# driverboard-v3.net
KiCad netlist of a schematic drawn in EAGLE
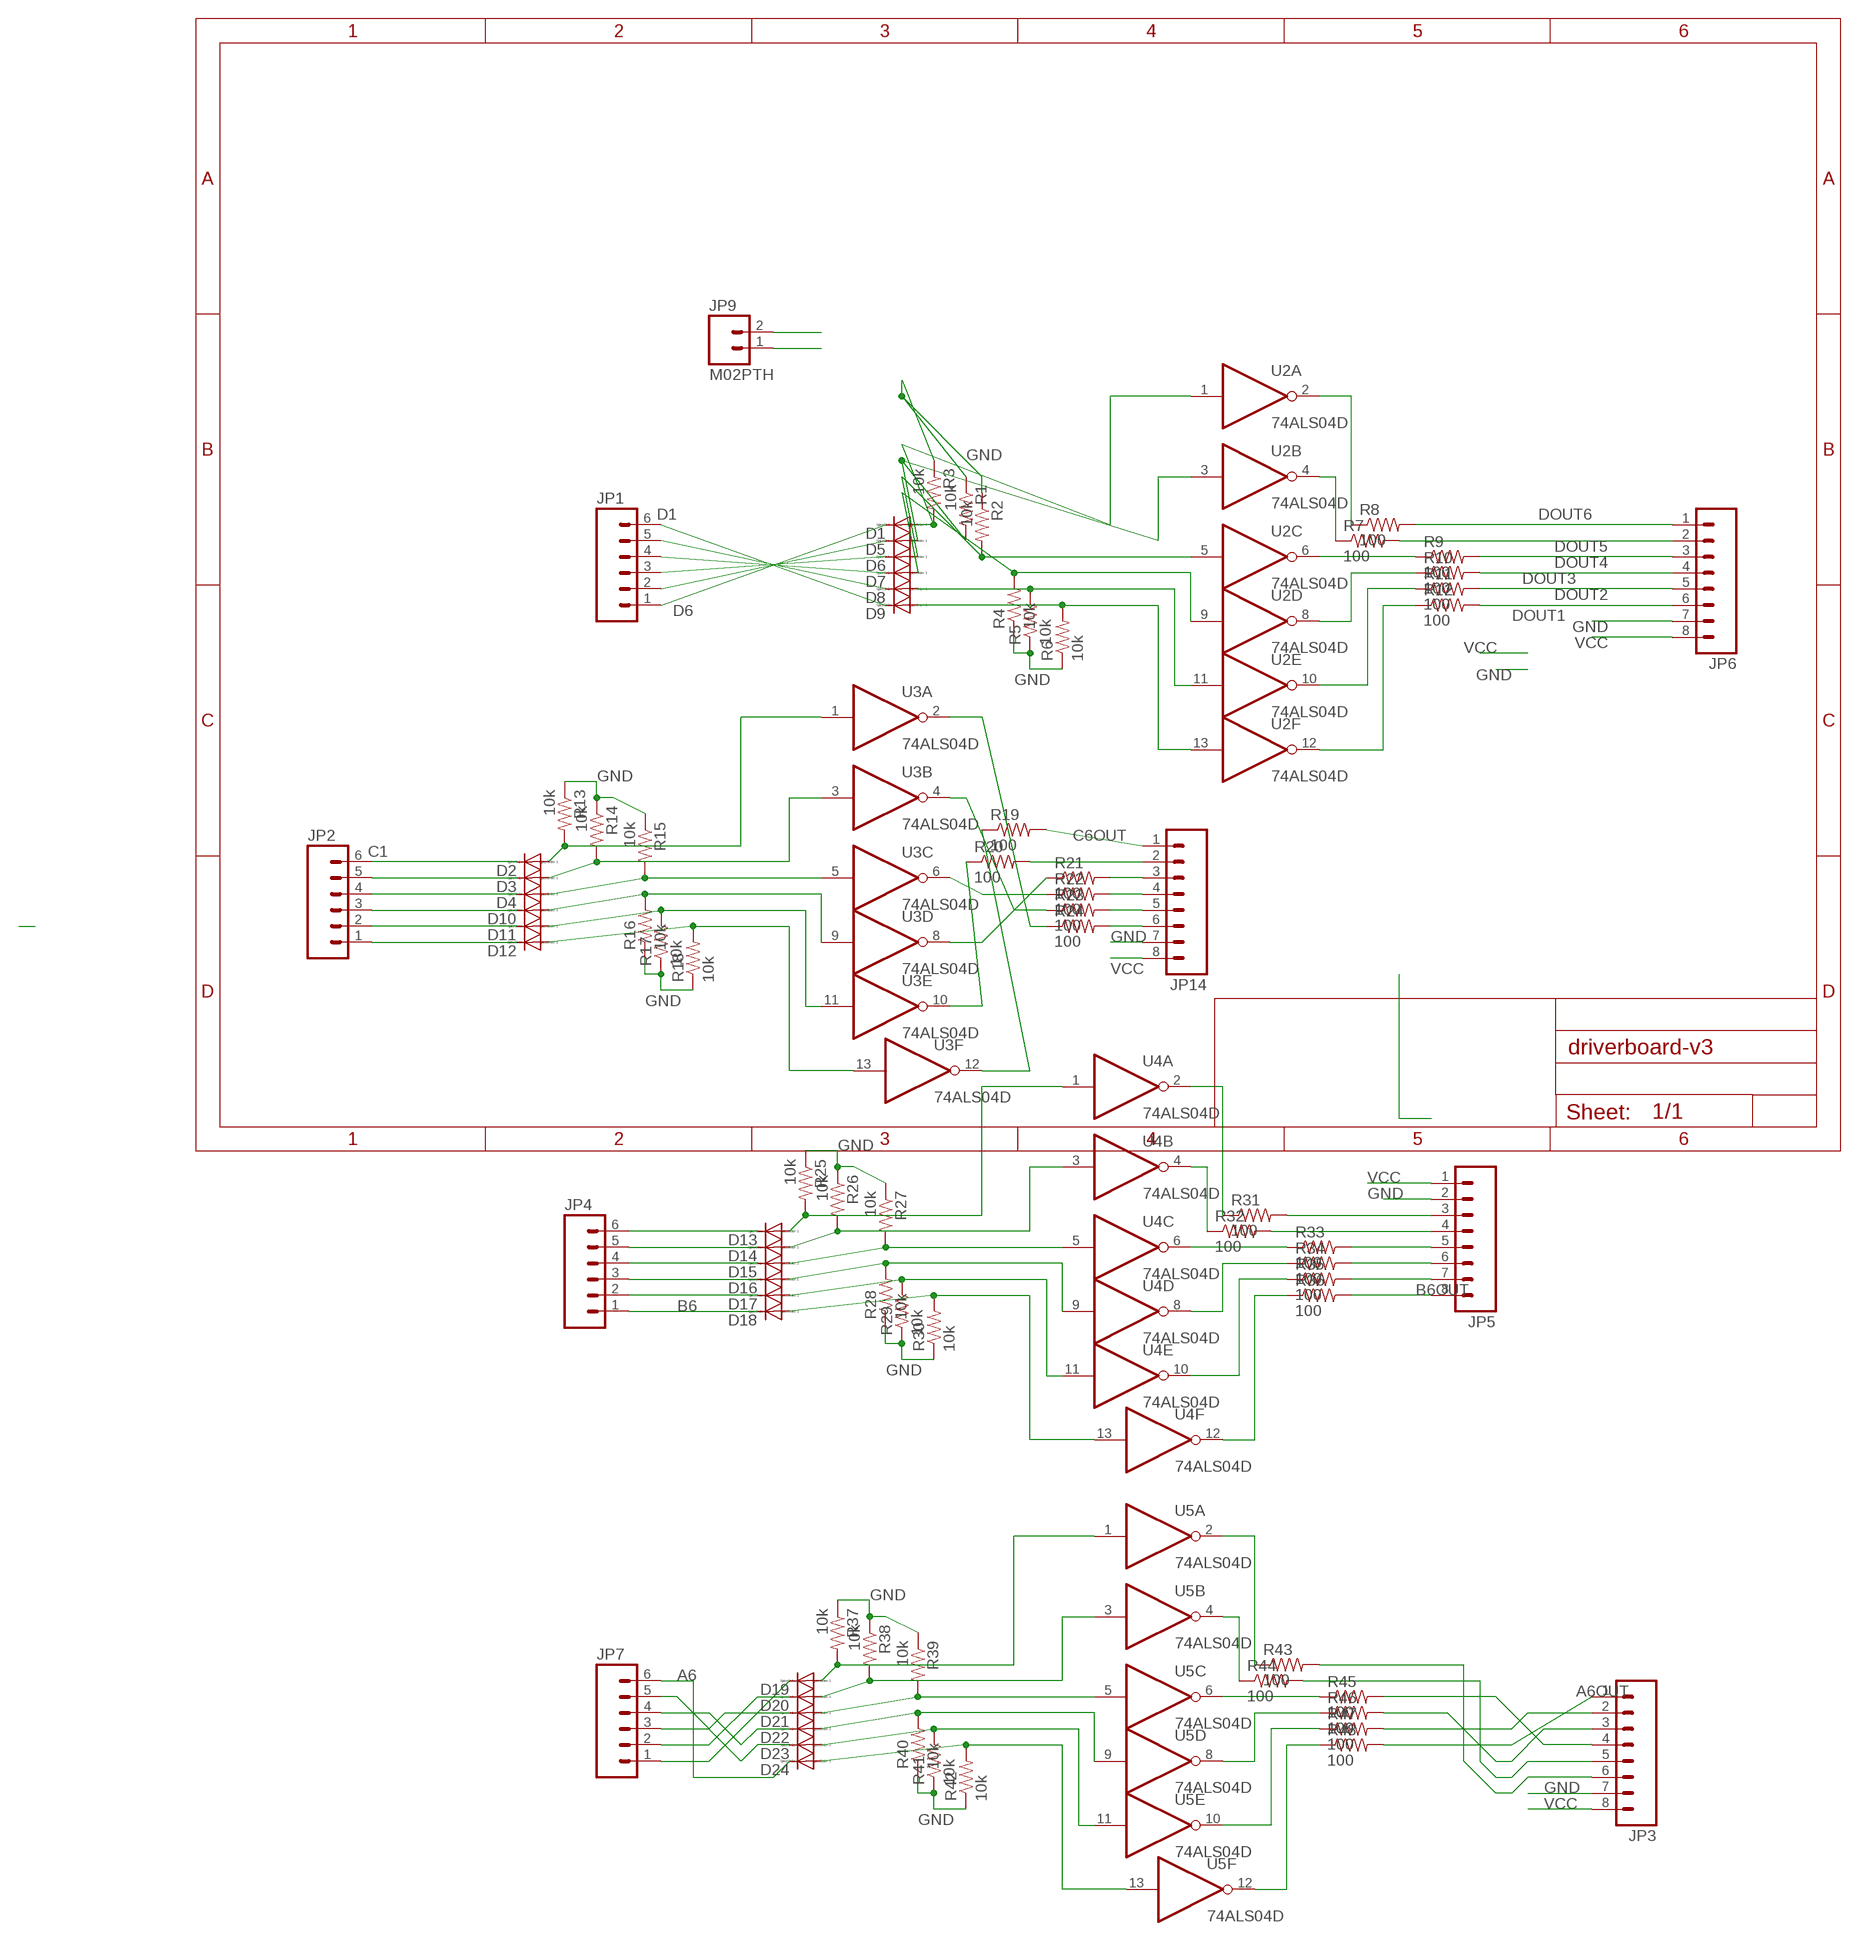
[diagram p0: schematic, sheet 1]

(export (version "E")
  (design (tool "Eeschema 10.0.6"))
  (components
    (comp (ref "D1")
      (value "DIODE-DO-214AC")
      (footprint "eagle-import:DO-214AC")
      (libsource (lib "eagle-import") (part "DIODE-DO-214AC"))
    )
    (comp (ref "D2")
      (value "DIODE-DO-214AC")
      (footprint "eagle-import:DO-214AC")
      (libsource (lib "eagle-import") (part "DIODE-DO-214AC"))
    )
    (comp (ref "D3")
      (value "DIODE-DO-214AC")
      (footprint "eagle-import:DO-214AC")
      (libsource (lib "eagle-import") (part "DIODE-DO-214AC"))
    )
    (comp (ref "D4")
      (value "DIODE-DO-214AC")
      (footprint "eagle-import:DO-214AC")
      (libsource (lib "eagle-import") (part "DIODE-DO-214AC"))
    )
    (comp (ref "D5")
      (value "DIODE-DO-214AC")
      (footprint "eagle-import:DO-214AC")
      (libsource (lib "eagle-import") (part "DIODE-DO-214AC"))
    )
    (comp (ref "D6")
      (value "DIODE-DO-214AC")
      (footprint "eagle-import:DO-214AC")
      (libsource (lib "eagle-import") (part "DIODE-DO-214AC"))
    )
    (comp (ref "D7")
      (value "DIODE-DO-214AC")
      (footprint "eagle-import:DO-214AC")
      (libsource (lib "eagle-import") (part "DIODE-DO-214AC"))
    )
    (comp (ref "D8")
      (value "DIODE-DO-214AC")
      (footprint "eagle-import:DO-214AC")
      (libsource (lib "eagle-import") (part "DIODE-DO-214AC"))
    )
    (comp (ref "D9")
      (value "DIODE-DO-214AC")
      (footprint "eagle-import:DO-214AC")
      (libsource (lib "eagle-import") (part "DIODE-DO-214AC"))
    )
    (comp (ref "D10")
      (value "DIODE-DO-214AC")
      (footprint "eagle-import:DO-214AC")
      (libsource (lib "eagle-import") (part "DIODE-DO-214AC"))
    )
    (comp (ref "D11")
      (value "DIODE-DO-214AC")
      (footprint "eagle-import:DO-214AC")
      (libsource (lib "eagle-import") (part "DIODE-DO-214AC"))
    )
    (comp (ref "D12")
      (value "DIODE-DO-214AC")
      (footprint "eagle-import:DO-214AC")
      (libsource (lib "eagle-import") (part "DIODE-DO-214AC"))
    )
    (comp (ref "D13")
      (value "DIODE-DO-214AC")
      (footprint "eagle-import:DO-214AC")
      (libsource (lib "eagle-import") (part "DIODE-DO-214AC"))
    )
    (comp (ref "D14")
      (value "DIODE-DO-214AC")
      (footprint "eagle-import:DO-214AC")
      (libsource (lib "eagle-import") (part "DIODE-DO-214AC"))
    )
    (comp (ref "D15")
      (value "DIODE-DO-214AC")
      (footprint "eagle-import:DO-214AC")
      (libsource (lib "eagle-import") (part "DIODE-DO-214AC"))
    )
    (comp (ref "D16")
      (value "DIODE-DO-214AC")
      (footprint "eagle-import:DO-214AC")
      (libsource (lib "eagle-import") (part "DIODE-DO-214AC"))
    )
    (comp (ref "D17")
      (value "DIODE-DO-214AC")
      (footprint "eagle-import:DO-214AC")
      (libsource (lib "eagle-import") (part "DIODE-DO-214AC"))
    )
    (comp (ref "D18")
      (value "DIODE-DO-214AC")
      (footprint "eagle-import:DO-214AC")
      (libsource (lib "eagle-import") (part "DIODE-DO-214AC"))
    )
    (comp (ref "D19")
      (value "DIODE-DO-214AC")
      (footprint "eagle-import:DO-214AC")
      (libsource (lib "eagle-import") (part "DIODE-DO-214AC"))
    )
    (comp (ref "D20")
      (value "DIODE-DO-214AC")
      (footprint "eagle-import:DO-214AC")
      (libsource (lib "eagle-import") (part "DIODE-DO-214AC"))
    )
    (comp (ref "D21")
      (value "DIODE-DO-214AC")
      (footprint "eagle-import:DO-214AC")
      (libsource (lib "eagle-import") (part "DIODE-DO-214AC"))
    )
    (comp (ref "D22")
      (value "DIODE-DO-214AC")
      (footprint "eagle-import:DO-214AC")
      (libsource (lib "eagle-import") (part "DIODE-DO-214AC"))
    )
    (comp (ref "D23")
      (value "DIODE-DO-214AC")
      (footprint "eagle-import:DO-214AC")
      (libsource (lib "eagle-import") (part "DIODE-DO-214AC"))
    )
    (comp (ref "D24")
      (value "DIODE-DO-214AC")
      (footprint "eagle-import:DO-214AC")
      (libsource (lib "eagle-import") (part "DIODE-DO-214AC"))
    )
    (comp (ref "JP1")
      (value "M06NO_SILK")
      (footprint "eagle-import:1X06_NO_SILK")
      (libsource (lib "eagle-import") (part "M06NO_SILK"))
    )
    (comp (ref "JP2")
      (value "M06NO_SILK")
      (footprint "eagle-import:1X06_NO_SILK")
      (libsource (lib "eagle-import") (part "M06NO_SILK"))
    )
    (comp (ref "JP3")
      (value "M08NO_SILK")
      (footprint "eagle-import:1X08_NO_SILK")
      (libsource (lib "eagle-import") (part "M08NO_SILK"))
    )
    (comp (ref "JP4")
      (value "M06NO_SILK")
      (footprint "eagle-import:1X06_NO_SILK")
      (libsource (lib "eagle-import") (part "M06NO_SILK"))
    )
    (comp (ref "JP5")
      (value "M08NO_SILK")
      (footprint "eagle-import:1X08_NO_SILK")
      (libsource (lib "eagle-import") (part "M08NO_SILK"))
    )
    (comp (ref "JP6")
      (value "M08NO_SILK")
      (footprint "eagle-import:1X08_NO_SILK")
      (libsource (lib "eagle-import") (part "M08NO_SILK"))
    )
    (comp (ref "JP7")
      (value "M06NO_SILK")
      (footprint "eagle-import:1X06_NO_SILK")
      (libsource (lib "eagle-import") (part "M06NO_SILK"))
    )
    (comp (ref "JP9")
      (value "M02PTH")
      (footprint "eagle-import:1X02")
      (libsource (lib "eagle-import") (part "M02PTH"))
    )
    (comp (ref "JP14")
      (value "M08NO_SILK")
      (footprint "eagle-import:1X08_NO_SILK")
      (libsource (lib "eagle-import") (part "M08NO_SILK"))
    )
    (comp (ref "R1")
      (value "10k")
      (footprint "eagle-import:0603-RES")
      (libsource (lib "eagle-import") (part "RESISTOR0603"))
    )
    (comp (ref "R2")
      (value "10k")
      (footprint "eagle-import:0603-RES")
      (libsource (lib "eagle-import") (part "RESISTOR0603"))
    )
    (comp (ref "R3")
      (value "10k")
      (footprint "eagle-import:0603-RES")
      (libsource (lib "eagle-import") (part "RESISTOR0603"))
    )
    (comp (ref "R4")
      (value "10k")
      (footprint "eagle-import:0603-RES")
      (libsource (lib "eagle-import") (part "RESISTOR0603"))
    )
    (comp (ref "R5")
      (value "10k")
      (footprint "eagle-import:0603-RES")
      (libsource (lib "eagle-import") (part "RESISTOR0603"))
    )
    (comp (ref "R6")
      (value "10k")
      (footprint "eagle-import:0603-RES")
      (libsource (lib "eagle-import") (part "RESISTOR0603"))
    )
    (comp (ref "R7")
      (value "100")
      (footprint "eagle-import:0603-RES")
      (libsource (lib "eagle-import") (part "RESISTOR0603"))
    )
    (comp (ref "R8")
      (value "100")
      (footprint "eagle-import:0603-RES")
      (libsource (lib "eagle-import") (part "RESISTOR0603"))
    )
    (comp (ref "R9")
      (value "100")
      (footprint "eagle-import:0603-RES")
      (libsource (lib "eagle-import") (part "RESISTOR0603"))
    )
    (comp (ref "R10")
      (value "100")
      (footprint "eagle-import:0603-RES")
      (libsource (lib "eagle-import") (part "RESISTOR0603"))
    )
    (comp (ref "R11")
      (value "100")
      (footprint "eagle-import:0603-RES")
      (libsource (lib "eagle-import") (part "RESISTOR0603"))
    )
    (comp (ref "R12")
      (value "100")
      (footprint "eagle-import:0603-RES")
      (libsource (lib "eagle-import") (part "RESISTOR0603"))
    )
    (comp (ref "R13")
      (value "10k")
      (footprint "eagle-import:0603-RES")
      (libsource (lib "eagle-import") (part "RESISTOR0603"))
    )
    (comp (ref "R14")
      (value "10k")
      (footprint "eagle-import:0603-RES")
      (libsource (lib "eagle-import") (part "RESISTOR0603"))
    )
    (comp (ref "R15")
      (value "10k")
      (footprint "eagle-import:0603-RES")
      (libsource (lib "eagle-import") (part "RESISTOR0603"))
    )
    (comp (ref "R16")
      (value "10k")
      (footprint "eagle-import:0603-RES")
      (libsource (lib "eagle-import") (part "RESISTOR0603"))
    )
    (comp (ref "R17")
      (value "10k")
      (footprint "eagle-import:0603-RES")
      (libsource (lib "eagle-import") (part "RESISTOR0603"))
    )
    (comp (ref "R18")
      (value "10k")
      (footprint "eagle-import:0603-RES")
      (libsource (lib "eagle-import") (part "RESISTOR0603"))
    )
    (comp (ref "R19")
      (value "100")
      (footprint "eagle-import:0603-RES")
      (libsource (lib "eagle-import") (part "RESISTOR0603"))
    )
    (comp (ref "R20")
      (value "100")
      (footprint "eagle-import:0603-RES")
      (libsource (lib "eagle-import") (part "RESISTOR0603"))
    )
    (comp (ref "R21")
      (value "100")
      (footprint "eagle-import:0603-RES")
      (libsource (lib "eagle-import") (part "RESISTOR0603"))
    )
    (comp (ref "R22")
      (value "100")
      (footprint "eagle-import:0603-RES")
      (libsource (lib "eagle-import") (part "RESISTOR0603"))
    )
    (comp (ref "R23")
      (value "100")
      (footprint "eagle-import:0603-RES")
      (libsource (lib "eagle-import") (part "RESISTOR0603"))
    )
    (comp (ref "R24")
      (value "100")
      (footprint "eagle-import:0603-RES")
      (libsource (lib "eagle-import") (part "RESISTOR0603"))
    )
    (comp (ref "R25")
      (value "10k")
      (footprint "eagle-import:0603-RES")
      (libsource (lib "eagle-import") (part "RESISTOR0603"))
    )
    (comp (ref "R26")
      (value "10k")
      (footprint "eagle-import:0603-RES")
      (libsource (lib "eagle-import") (part "RESISTOR0603"))
    )
    (comp (ref "R27")
      (value "10k")
      (footprint "eagle-import:0603-RES")
      (libsource (lib "eagle-import") (part "RESISTOR0603"))
    )
    (comp (ref "R28")
      (value "10k")
      (footprint "eagle-import:0603-RES")
      (libsource (lib "eagle-import") (part "RESISTOR0603"))
    )
    (comp (ref "R29")
      (value "10k")
      (footprint "eagle-import:0603-RES")
      (libsource (lib "eagle-import") (part "RESISTOR0603"))
    )
    (comp (ref "R30")
      (value "10k")
      (footprint "eagle-import:0603-RES")
      (libsource (lib "eagle-import") (part "RESISTOR0603"))
    )
    (comp (ref "R31")
      (value "100")
      (footprint "eagle-import:0603-RES")
      (libsource (lib "eagle-import") (part "RESISTOR0603"))
    )
    (comp (ref "R32")
      (value "100")
      (footprint "eagle-import:0603-RES")
      (libsource (lib "eagle-import") (part "RESISTOR0603"))
    )
    (comp (ref "R33")
      (value "100")
      (footprint "eagle-import:0603-RES")
      (libsource (lib "eagle-import") (part "RESISTOR0603"))
    )
    (comp (ref "R34")
      (value "100")
      (footprint "eagle-import:0603-RES")
      (libsource (lib "eagle-import") (part "RESISTOR0603"))
    )
    (comp (ref "R35")
      (value "100")
      (footprint "eagle-import:0603-RES")
      (libsource (lib "eagle-import") (part "RESISTOR0603"))
    )
    (comp (ref "R36")
      (value "100")
      (footprint "eagle-import:0603-RES")
      (libsource (lib "eagle-import") (part "RESISTOR0603"))
    )
    (comp (ref "R37")
      (value "10k")
      (footprint "eagle-import:0603-RES")
      (libsource (lib "eagle-import") (part "RESISTOR0603"))
    )
    (comp (ref "R38")
      (value "10k")
      (footprint "eagle-import:0603-RES")
      (libsource (lib "eagle-import") (part "RESISTOR0603"))
    )
    (comp (ref "R39")
      (value "10k")
      (footprint "eagle-import:0603-RES")
      (libsource (lib "eagle-import") (part "RESISTOR0603"))
    )
    (comp (ref "R40")
      (value "10k")
      (footprint "eagle-import:0603-RES")
      (libsource (lib "eagle-import") (part "RESISTOR0603"))
    )
    (comp (ref "R41")
      (value "10k")
      (footprint "eagle-import:0603-RES")
      (libsource (lib "eagle-import") (part "RESISTOR0603"))
    )
    (comp (ref "R42")
      (value "10k")
      (footprint "eagle-import:0603-RES")
      (libsource (lib "eagle-import") (part "RESISTOR0603"))
    )
    (comp (ref "R43")
      (value "100")
      (footprint "eagle-import:0603-RES")
      (libsource (lib "eagle-import") (part "RESISTOR0603"))
    )
    (comp (ref "R44")
      (value "100")
      (footprint "eagle-import:0603-RES")
      (libsource (lib "eagle-import") (part "RESISTOR0603"))
    )
    (comp (ref "R45")
      (value "100")
      (footprint "eagle-import:0603-RES")
      (libsource (lib "eagle-import") (part "RESISTOR0603"))
    )
    (comp (ref "R46")
      (value "100")
      (footprint "eagle-import:0603-RES")
      (libsource (lib "eagle-import") (part "RESISTOR0603"))
    )
    (comp (ref "R47")
      (value "100")
      (footprint "eagle-import:0603-RES")
      (libsource (lib "eagle-import") (part "RESISTOR0603"))
    )
    (comp (ref "R48")
      (value "100")
      (footprint "eagle-import:0603-RES")
      (libsource (lib "eagle-import") (part "RESISTOR0603"))
    )
    (comp (ref "U2")
      (value "74ALS04D")
      (footprint "eagle-import:SO14")
      (libsource (lib "eagle-import") (part "7404DALS"))
    )
    (comp (ref "U3")
      (value "74ALS04D")
      (footprint "eagle-import:SO14")
      (libsource (lib "eagle-import") (part "7404DALS"))
    )
    (comp (ref "U4")
      (value "74ALS04D")
      (footprint "eagle-import:SO14")
      (libsource (lib "eagle-import") (part "7404DALS"))
    )
    (comp (ref "U5")
      (value "74ALS04D")
      (footprint "eagle-import:SO14")
      (libsource (lib "eagle-import") (part "7404DALS"))
    )
  )
  (nets
    (net (code "1") (name "/A6") (class "Default")
      (node (ref "D24") (pin "C") (pinfunction "C_C") (pintype "passive"))
      (node (ref "JP7") (pin "6") (pinfunction "6_6") (pintype "passive"))
    )
    (net (code "2") (name "/A6OUT") (class "Default")
      (node (ref "JP3") (pin "1") (pinfunction "1_1") (pintype "passive"))
      (node (ref "R48") (pin "2") (pinfunction "2_2") (pintype "passive"))
    )
    (net (code "3") (name "/B6") (class "Default")
      (node (ref "D18") (pin "C") (pinfunction "C_C") (pintype "passive"))
      (node (ref "JP4") (pin "1") (pinfunction "1_1") (pintype "passive"))
    )
    (net (code "4") (name "/B6OUT") (class "Default")
      (node (ref "JP5") (pin "8") (pinfunction "8_8") (pintype "passive"))
      (node (ref "R36") (pin "2") (pinfunction "2_2") (pintype "passive"))
    )
    (net (code "5") (name "/C1") (class "Default")
      (node (ref "D2") (pin "C") (pinfunction "C_C") (pintype "passive"))
      (node (ref "JP2") (pin "6") (pinfunction "6_6") (pintype "passive"))
    )
    (net (code "6") (name "/C6OUT") (class "Default")
      (node (ref "JP14") (pin "1") (pinfunction "1_1") (pintype "passive"))
      (node (ref "R19") (pin "2") (pinfunction "2_2") (pintype "passive"))
    )
    (net (code "7") (name "/D1") (class "Default")
      (node (ref "D9") (pin "C") (pinfunction "C_C") (pintype "passive"))
      (node (ref "JP1") (pin "6") (pinfunction "6_6") (pintype "passive"))
    )
    (net (code "8") (name "/D6") (class "Default")
      (node (ref "D1") (pin "C") (pinfunction "C_C") (pintype "passive"))
      (node (ref "JP1") (pin "1") (pinfunction "1_1") (pintype "passive"))
    )
    (net (code "9") (name "/DOUT1") (class "Default")
      (node (ref "JP6") (pin "6") (pinfunction "6_6") (pintype "passive"))
      (node (ref "R12") (pin "2") (pinfunction "2_2") (pintype "passive"))
    )
    (net (code "10") (name "/DOUT2") (class "Default")
      (node (ref "JP6") (pin "5") (pinfunction "5_5") (pintype "passive"))
      (node (ref "R11") (pin "2") (pinfunction "2_2") (pintype "passive"))
    )
    (net (code "11") (name "/DOUT3") (class "Default")
      (node (ref "JP6") (pin "4") (pinfunction "4_4") (pintype "passive"))
      (node (ref "R10") (pin "2") (pinfunction "2_2") (pintype "passive"))
    )
    (net (code "12") (name "/DOUT4") (class "Default")
      (node (ref "JP6") (pin "3") (pinfunction "3_3") (pintype "passive"))
      (node (ref "R9") (pin "2") (pinfunction "2_2") (pintype "passive"))
    )
    (net (code "13") (name "/DOUT5") (class "Default")
      (node (ref "JP6") (pin "2") (pinfunction "2_2") (pintype "passive"))
      (node (ref "R7") (pin "2") (pinfunction "2_2") (pintype "passive"))
    )
    (net (code "14") (name "/DOUT6") (class "Default")
      (node (ref "JP6") (pin "1") (pinfunction "1_1") (pintype "passive"))
      (node (ref "R8") (pin "2") (pinfunction "2_2") (pintype "passive"))
    )
    (net (code "15") (name "/GND") (class "Default")
      (node (ref "JP14") (pin "7") (pinfunction "7_7") (pintype "passive"))
      (node (ref "JP3") (pin "7") (pinfunction "7_7") (pintype "passive"))
      (node (ref "JP5") (pin "2") (pinfunction "2_2") (pintype "passive"))
      (node (ref "JP6") (pin "7") (pinfunction "7_7") (pintype "passive"))
      (node (ref "JP9") (pin "1") (pinfunction "1_1") (pintype "passive"))
      (node (ref "R1") (pin "1") (pinfunction "1_1") (pintype "passive"))
      (node (ref "R13") (pin "1") (pinfunction "1_1") (pintype "passive"))
      (node (ref "R14") (pin "1") (pinfunction "1_1") (pintype "passive"))
      (node (ref "R15") (pin "1") (pinfunction "1_1") (pintype "passive"))
      (node (ref "R16") (pin "1") (pinfunction "1_1") (pintype "passive"))
      (node (ref "R17") (pin "1") (pinfunction "1_1") (pintype "passive"))
      (node (ref "R18") (pin "1") (pinfunction "1_1") (pintype "passive"))
      (node (ref "R2") (pin "1") (pinfunction "1_1") (pintype "passive"))
      (node (ref "R25") (pin "1") (pinfunction "1_1") (pintype "passive"))
      (node (ref "R26") (pin "1") (pinfunction "1_1") (pintype "passive"))
      (node (ref "R27") (pin "1") (pinfunction "1_1") (pintype "passive"))
      (node (ref "R28") (pin "1") (pinfunction "1_1") (pintype "passive"))
      (node (ref "R29") (pin "1") (pinfunction "1_1") (pintype "passive"))
      (node (ref "R3") (pin "1") (pinfunction "1_1") (pintype "passive"))
      (node (ref "R30") (pin "1") (pinfunction "1_1") (pintype "passive"))
      (node (ref "R37") (pin "1") (pinfunction "1_1") (pintype "passive"))
      (node (ref "R38") (pin "1") (pinfunction "1_1") (pintype "passive"))
      (node (ref "R39") (pin "1") (pinfunction "1_1") (pintype "passive"))
      (node (ref "R4") (pin "1") (pinfunction "1_1") (pintype "passive"))
      (node (ref "R40") (pin "1") (pinfunction "1_1") (pintype "passive"))
      (node (ref "R41") (pin "1") (pinfunction "1_1") (pintype "passive"))
      (node (ref "R42") (pin "1") (pinfunction "1_1") (pintype "passive"))
      (node (ref "R5") (pin "1") (pinfunction "1_1") (pintype "passive"))
      (node (ref "R6") (pin "1") (pinfunction "1_1") (pintype "passive"))
    )
    (net (code "16") (name "/VCC") (class "Default")
      (node (ref "JP14") (pin "8") (pinfunction "8_8") (pintype "passive"))
      (node (ref "JP3") (pin "8") (pinfunction "8_8") (pintype "passive"))
      (node (ref "JP5") (pin "1") (pinfunction "1_1") (pintype "passive"))
      (node (ref "JP6") (pin "8") (pinfunction "8_8") (pintype "passive"))
      (node (ref "JP9") (pin "2") (pinfunction "2_2") (pintype "passive"))
    )
    (net (code "17") (name "Net-(D3-PadC)") (class "Default")
      (node (ref "D3") (pin "C") (pinfunction "C_C") (pintype "passive"))
      (node (ref "JP2") (pin "5") (pinfunction "5_5") (pintype "passive"))
    )
    (net (code "18") (name "Net-(D4-PadC)") (class "Default")
      (node (ref "D4") (pin "C") (pinfunction "C_C") (pintype "passive"))
      (node (ref "JP2") (pin "4") (pinfunction "4_4") (pintype "passive"))
    )
    (net (code "19") (name "Net-(D5-PadC)") (class "Default")
      (node (ref "D5") (pin "C") (pinfunction "C_C") (pintype "passive"))
      (node (ref "JP1") (pin "2") (pinfunction "2_2") (pintype "passive"))
    )
    (net (code "20") (name "Net-(D6-PadC)") (class "Default")
      (node (ref "D6") (pin "C") (pinfunction "C_C") (pintype "passive"))
      (node (ref "JP1") (pin "3") (pinfunction "3_3") (pintype "passive"))
    )
    (net (code "21") (name "Net-(D7-PadC)") (class "Default")
      (node (ref "D7") (pin "C") (pinfunction "C_C") (pintype "passive"))
      (node (ref "JP1") (pin "4") (pinfunction "4_4") (pintype "passive"))
    )
    (net (code "22") (name "Net-(D8-PadC)") (class "Default")
      (node (ref "D8") (pin "C") (pinfunction "C_C") (pintype "passive"))
      (node (ref "JP1") (pin "5") (pinfunction "5_5") (pintype "passive"))
    )
    (net (code "23") (name "Net-(D10-PadC)") (class "Default")
      (node (ref "D10") (pin "C") (pinfunction "C_C") (pintype "passive"))
      (node (ref "JP2") (pin "3") (pinfunction "3_3") (pintype "passive"))
    )
    (net (code "24") (name "Net-(D11-PadC)") (class "Default")
      (node (ref "D11") (pin "C") (pinfunction "C_C") (pintype "passive"))
      (node (ref "JP2") (pin "2") (pinfunction "2_2") (pintype "passive"))
    )
    (net (code "25") (name "Net-(D12-PadC)") (class "Default")
      (node (ref "D12") (pin "C") (pinfunction "C_C") (pintype "passive"))
      (node (ref "JP2") (pin "1") (pinfunction "1_1") (pintype "passive"))
    )
    (net (code "26") (name "Net-(D13-PadC)") (class "Default")
      (node (ref "D13") (pin "C") (pinfunction "C_C") (pintype "passive"))
      (node (ref "JP4") (pin "6") (pinfunction "6_6") (pintype "passive"))
    )
    (net (code "27") (name "Net-(D14-PadC)") (class "Default")
      (node (ref "D14") (pin "C") (pinfunction "C_C") (pintype "passive"))
      (node (ref "JP4") (pin "5") (pinfunction "5_5") (pintype "passive"))
    )
    (net (code "28") (name "Net-(D15-PadC)") (class "Default")
      (node (ref "D15") (pin "C") (pinfunction "C_C") (pintype "passive"))
      (node (ref "JP4") (pin "4") (pinfunction "4_4") (pintype "passive"))
    )
    (net (code "29") (name "Net-(D16-PadC)") (class "Default")
      (node (ref "D16") (pin "C") (pinfunction "C_C") (pintype "passive"))
      (node (ref "JP4") (pin "3") (pinfunction "3_3") (pintype "passive"))
    )
    (net (code "30") (name "Net-(D17-PadC)") (class "Default")
      (node (ref "D17") (pin "C") (pinfunction "C_C") (pintype "passive"))
      (node (ref "JP4") (pin "2") (pinfunction "2_2") (pintype "passive"))
    )
    (net (code "31") (name "Net-(D19-PadC)") (class "Default")
      (node (ref "D19") (pin "C") (pinfunction "C_C") (pintype "passive"))
      (node (ref "JP7") (pin "1") (pinfunction "1_1") (pintype "passive"))
    )
    (net (code "32") (name "Net-(D20-PadC)") (class "Default")
      (node (ref "D20") (pin "C") (pinfunction "C_C") (pintype "passive"))
      (node (ref "JP7") (pin "2") (pinfunction "2_2") (pintype "passive"))
    )
    (net (code "33") (name "Net-(D21-PadC)") (class "Default")
      (node (ref "D21") (pin "C") (pinfunction "C_C") (pintype "passive"))
      (node (ref "JP7") (pin "3") (pinfunction "3_3") (pintype "passive"))
    )
    (net (code "34") (name "Net-(D22-PadC)") (class "Default")
      (node (ref "D22") (pin "C") (pinfunction "C_C") (pintype "passive"))
      (node (ref "JP7") (pin "4") (pinfunction "4_4") (pintype "passive"))
    )
    (net (code "35") (name "Net-(D23-PadC)") (class "Default")
      (node (ref "D23") (pin "C") (pinfunction "C_C") (pintype "passive"))
      (node (ref "JP7") (pin "5") (pinfunction "5_5") (pintype "passive"))
    )
    (net (code "36") (name "Net-(JP3-Pad2)") (class "Default")
      (node (ref "JP3") (pin "2") (pinfunction "2_2") (pintype "passive"))
      (node (ref "R47") (pin "2") (pinfunction "2_2") (pintype "passive"))
    )
    (net (code "37") (name "Net-(JP3-Pad3)") (class "Default")
      (node (ref "JP3") (pin "3") (pinfunction "3_3") (pintype "passive"))
      (node (ref "R46") (pin "2") (pinfunction "2_2") (pintype "passive"))
    )
    (net (code "38") (name "Net-(JP3-Pad4)") (class "Default")
      (node (ref "JP3") (pin "4") (pinfunction "4_4") (pintype "passive"))
      (node (ref "R45") (pin "2") (pinfunction "2_2") (pintype "passive"))
    )
    (net (code "39") (name "Net-(JP3-Pad5)") (class "Default")
      (node (ref "JP3") (pin "5") (pinfunction "5_5") (pintype "passive"))
      (node (ref "R44") (pin "2") (pinfunction "2_2") (pintype "passive"))
    )
    (net (code "40") (name "Net-(JP3-Pad6)") (class "Default")
      (node (ref "JP3") (pin "6") (pinfunction "6_6") (pintype "passive"))
      (node (ref "R43") (pin "2") (pinfunction "2_2") (pintype "passive"))
    )
    (net (code "41") (name "Net-(JP5-Pad3)") (class "Default")
      (node (ref "JP5") (pin "3") (pinfunction "3_3") (pintype "passive"))
      (node (ref "R31") (pin "2") (pinfunction "2_2") (pintype "passive"))
    )
    (net (code "42") (name "Net-(JP5-Pad4)") (class "Default")
      (node (ref "JP5") (pin "4") (pinfunction "4_4") (pintype "passive"))
      (node (ref "R32") (pin "2") (pinfunction "2_2") (pintype "passive"))
    )
    (net (code "43") (name "Net-(JP5-Pad5)") (class "Default")
      (node (ref "JP5") (pin "5") (pinfunction "5_5") (pintype "passive"))
      (node (ref "R33") (pin "2") (pinfunction "2_2") (pintype "passive"))
    )
    (net (code "44") (name "Net-(JP5-Pad6)") (class "Default")
      (node (ref "JP5") (pin "6") (pinfunction "6_6") (pintype "passive"))
      (node (ref "R34") (pin "2") (pinfunction "2_2") (pintype "passive"))
    )
    (net (code "45") (name "Net-(JP5-Pad7)") (class "Default")
      (node (ref "JP5") (pin "7") (pinfunction "7_7") (pintype "passive"))
      (node (ref "R35") (pin "2") (pinfunction "2_2") (pintype "passive"))
    )
    (net (code "46") (name "Net-(JP14-Pad2)") (class "Default")
      (node (ref "JP14") (pin "2") (pinfunction "2_2") (pintype "passive"))
      (node (ref "R20") (pin "2") (pinfunction "2_2") (pintype "passive"))
    )
    (net (code "47") (name "Net-(JP14-Pad3)") (class "Default")
      (node (ref "JP14") (pin "3") (pinfunction "3_3") (pintype "passive"))
      (node (ref "R21") (pin "2") (pinfunction "2_2") (pintype "passive"))
    )
    (net (code "48") (name "Net-(JP14-Pad4)") (class "Default")
      (node (ref "JP14") (pin "4") (pinfunction "4_4") (pintype "passive"))
      (node (ref "R22") (pin "2") (pinfunction "2_2") (pintype "passive"))
    )
    (net (code "49") (name "Net-(JP14-Pad5)") (class "Default")
      (node (ref "JP14") (pin "5") (pinfunction "5_5") (pintype "passive"))
      (node (ref "R23") (pin "2") (pinfunction "2_2") (pintype "passive"))
    )
    (net (code "50") (name "Net-(JP14-Pad6)") (class "Default")
      (node (ref "JP14") (pin "6") (pinfunction "6_6") (pintype "passive"))
      (node (ref "R24") (pin "2") (pinfunction "2_2") (pintype "passive"))
    )
    (net (code "51") (name "Net-(U2A-I)") (class "Default")
      (node (ref "D1") (pin "A") (pinfunction "A_A") (pintype "passive"))
      (node (ref "R3") (pin "2") (pinfunction "2_2") (pintype "passive"))
      (node (ref "U2") (pin "1") (pinfunction "I_1") (pintype "input"))
    )
    (net (code "52") (name "Net-(U2A-O)") (class "Default")
      (node (ref "R8") (pin "1") (pinfunction "1_1") (pintype "passive"))
      (node (ref "U2") (pin "2") (pinfunction "O_2") (pintype "output"))
    )
    (net (code "53") (name "Net-(U2B-I)") (class "Default")
      (node (ref "D5") (pin "A") (pinfunction "A_A") (pintype "passive"))
      (node (ref "R1") (pin "2") (pinfunction "2_2") (pintype "passive"))
      (node (ref "U2") (pin "3") (pinfunction "I_3") (pintype "input"))
    )
    (net (code "54") (name "Net-(U2B-O)") (class "Default")
      (node (ref "R7") (pin "1") (pinfunction "1_1") (pintype "passive"))
      (node (ref "U2") (pin "4") (pinfunction "O_4") (pintype "output"))
    )
    (net (code "55") (name "Net-(U2C-I)") (class "Default")
      (node (ref "D6") (pin "A") (pinfunction "A_A") (pintype "passive"))
      (node (ref "R2") (pin "2") (pinfunction "2_2") (pintype "passive"))
      (node (ref "U2") (pin "5") (pinfunction "I_5") (pintype "input"))
    )
    (net (code "56") (name "Net-(U2C-O)") (class "Default")
      (node (ref "R9") (pin "1") (pinfunction "1_1") (pintype "passive"))
      (node (ref "U2") (pin "6") (pinfunction "O_6") (pintype "output"))
    )
    (net (code "57") (name "Net-(U2D-I)") (class "Default")
      (node (ref "D7") (pin "A") (pinfunction "A_A") (pintype "passive"))
      (node (ref "R4") (pin "2") (pinfunction "2_2") (pintype "passive"))
      (node (ref "U2") (pin "9") (pinfunction "I_9") (pintype "input"))
    )
    (net (code "58") (name "Net-(U2D-O)") (class "Default")
      (node (ref "R10") (pin "1") (pinfunction "1_1") (pintype "passive"))
      (node (ref "U2") (pin "8") (pinfunction "O_8") (pintype "output"))
    )
    (net (code "59") (name "Net-(U2E-I)") (class "Default")
      (node (ref "D8") (pin "A") (pinfunction "A_A") (pintype "passive"))
      (node (ref "R5") (pin "2") (pinfunction "2_2") (pintype "passive"))
      (node (ref "U2") (pin "11") (pinfunction "I_11") (pintype "input"))
    )
    (net (code "60") (name "Net-(U2E-O)") (class "Default")
      (node (ref "R11") (pin "1") (pinfunction "1_1") (pintype "passive"))
      (node (ref "U2") (pin "10") (pinfunction "O_10") (pintype "output"))
    )
    (net (code "61") (name "Net-(U2F-I)") (class "Default")
      (node (ref "D9") (pin "A") (pinfunction "A_A") (pintype "passive"))
      (node (ref "R6") (pin "2") (pinfunction "2_2") (pintype "passive"))
      (node (ref "U2") (pin "13") (pinfunction "I_13") (pintype "input"))
    )
    (net (code "62") (name "Net-(U2F-O)") (class "Default")
      (node (ref "R12") (pin "1") (pinfunction "1_1") (pintype "passive"))
      (node (ref "U2") (pin "12") (pinfunction "O_12") (pintype "output"))
    )
    (net (code "63") (name "Net-(U3A-I)") (class "Default")
      (node (ref "D2") (pin "A") (pinfunction "A_A") (pintype "passive"))
      (node (ref "R13") (pin "2") (pinfunction "2_2") (pintype "passive"))
      (node (ref "U3") (pin "1") (pinfunction "I_1") (pintype "input"))
    )
    (net (code "64") (name "Net-(U3A-O)") (class "Default")
      (node (ref "R24") (pin "1") (pinfunction "1_1") (pintype "passive"))
      (node (ref "U3") (pin "2") (pinfunction "O_2") (pintype "output"))
    )
    (net (code "65") (name "Net-(U3B-I)") (class "Default")
      (node (ref "D3") (pin "A") (pinfunction "A_A") (pintype "passive"))
      (node (ref "R14") (pin "2") (pinfunction "2_2") (pintype "passive"))
      (node (ref "U3") (pin "3") (pinfunction "I_3") (pintype "input"))
    )
    (net (code "66") (name "Net-(U3B-O)") (class "Default")
      (node (ref "R23") (pin "1") (pinfunction "1_1") (pintype "passive"))
      (node (ref "U3") (pin "4") (pinfunction "O_4") (pintype "output"))
    )
    (net (code "67") (name "Net-(U3C-I)") (class "Default")
      (node (ref "D4") (pin "A") (pinfunction "A_A") (pintype "passive"))
      (node (ref "R15") (pin "2") (pinfunction "2_2") (pintype "passive"))
      (node (ref "U3") (pin "5") (pinfunction "I_5") (pintype "input"))
    )
    (net (code "68") (name "Net-(U3C-O)") (class "Default")
      (node (ref "R22") (pin "1") (pinfunction "1_1") (pintype "passive"))
      (node (ref "U3") (pin "6") (pinfunction "O_6") (pintype "output"))
    )
    (net (code "69") (name "Net-(U3D-I)") (class "Default")
      (node (ref "D10") (pin "A") (pinfunction "A_A") (pintype "passive"))
      (node (ref "R16") (pin "2") (pinfunction "2_2") (pintype "passive"))
      (node (ref "U3") (pin "9") (pinfunction "I_9") (pintype "input"))
    )
    (net (code "70") (name "Net-(U3D-O)") (class "Default")
      (node (ref "R21") (pin "1") (pinfunction "1_1") (pintype "passive"))
      (node (ref "U3") (pin "8") (pinfunction "O_8") (pintype "output"))
    )
    (net (code "71") (name "Net-(U3E-I)") (class "Default")
      (node (ref "D11") (pin "A") (pinfunction "A_A") (pintype "passive"))
      (node (ref "R17") (pin "2") (pinfunction "2_2") (pintype "passive"))
      (node (ref "U3") (pin "11") (pinfunction "I_11") (pintype "input"))
    )
    (net (code "72") (name "Net-(U3E-O)") (class "Default")
      (node (ref "R20") (pin "1") (pinfunction "1_1") (pintype "passive"))
      (node (ref "U3") (pin "10") (pinfunction "O_10") (pintype "output"))
    )
    (net (code "73") (name "Net-(U3F-I)") (class "Default")
      (node (ref "D12") (pin "A") (pinfunction "A_A") (pintype "passive"))
      (node (ref "R18") (pin "2") (pinfunction "2_2") (pintype "passive"))
      (node (ref "U3") (pin "13") (pinfunction "I_13") (pintype "input"))
    )
    (net (code "74") (name "Net-(U3F-O)") (class "Default")
      (node (ref "R19") (pin "1") (pinfunction "1_1") (pintype "passive"))
      (node (ref "U3") (pin "12") (pinfunction "O_12") (pintype "output"))
    )
    (net (code "75") (name "Net-(U4A-I)") (class "Default")
      (node (ref "D13") (pin "A") (pinfunction "A_A") (pintype "passive"))
      (node (ref "R25") (pin "2") (pinfunction "2_2") (pintype "passive"))
      (node (ref "U4") (pin "1") (pinfunction "I_1") (pintype "input"))
    )
    (net (code "76") (name "Net-(U4A-O)") (class "Default")
      (node (ref "R31") (pin "1") (pinfunction "1_1") (pintype "passive"))
      (node (ref "U4") (pin "2") (pinfunction "O_2") (pintype "output"))
    )
    (net (code "77") (name "Net-(U4B-I)") (class "Default")
      (node (ref "D14") (pin "A") (pinfunction "A_A") (pintype "passive"))
      (node (ref "R26") (pin "2") (pinfunction "2_2") (pintype "passive"))
      (node (ref "U4") (pin "3") (pinfunction "I_3") (pintype "input"))
    )
    (net (code "78") (name "Net-(U4B-O)") (class "Default")
      (node (ref "R32") (pin "1") (pinfunction "1_1") (pintype "passive"))
      (node (ref "U4") (pin "4") (pinfunction "O_4") (pintype "output"))
    )
    (net (code "79") (name "Net-(U4C-I)") (class "Default")
      (node (ref "D15") (pin "A") (pinfunction "A_A") (pintype "passive"))
      (node (ref "R27") (pin "2") (pinfunction "2_2") (pintype "passive"))
      (node (ref "U4") (pin "5") (pinfunction "I_5") (pintype "input"))
    )
    (net (code "80") (name "Net-(U4C-O)") (class "Default")
      (node (ref "R33") (pin "1") (pinfunction "1_1") (pintype "passive"))
      (node (ref "U4") (pin "6") (pinfunction "O_6") (pintype "output"))
    )
    (net (code "81") (name "Net-(U4D-I)") (class "Default")
      (node (ref "D16") (pin "A") (pinfunction "A_A") (pintype "passive"))
      (node (ref "R28") (pin "2") (pinfunction "2_2") (pintype "passive"))
      (node (ref "U4") (pin "9") (pinfunction "I_9") (pintype "input"))
    )
    (net (code "82") (name "Net-(U4D-O)") (class "Default")
      (node (ref "R34") (pin "1") (pinfunction "1_1") (pintype "passive"))
      (node (ref "U4") (pin "8") (pinfunction "O_8") (pintype "output"))
    )
    (net (code "83") (name "Net-(U4E-I)") (class "Default")
      (node (ref "D17") (pin "A") (pinfunction "A_A") (pintype "passive"))
      (node (ref "R29") (pin "2") (pinfunction "2_2") (pintype "passive"))
      (node (ref "U4") (pin "11") (pinfunction "I_11") (pintype "input"))
    )
    (net (code "84") (name "Net-(U4E-O)") (class "Default")
      (node (ref "R35") (pin "1") (pinfunction "1_1") (pintype "passive"))
      (node (ref "U4") (pin "10") (pinfunction "O_10") (pintype "output"))
    )
    (net (code "85") (name "Net-(U4F-I)") (class "Default")
      (node (ref "D18") (pin "A") (pinfunction "A_A") (pintype "passive"))
      (node (ref "R30") (pin "2") (pinfunction "2_2") (pintype "passive"))
      (node (ref "U4") (pin "13") (pinfunction "I_13") (pintype "input"))
    )
    (net (code "86") (name "Net-(U4F-O)") (class "Default")
      (node (ref "R36") (pin "1") (pinfunction "1_1") (pintype "passive"))
      (node (ref "U4") (pin "12") (pinfunction "O_12") (pintype "output"))
    )
    (net (code "87") (name "Net-(U5A-I)") (class "Default")
      (node (ref "D19") (pin "A") (pinfunction "A_A") (pintype "passive"))
      (node (ref "R37") (pin "2") (pinfunction "2_2") (pintype "passive"))
      (node (ref "U5") (pin "1") (pinfunction "I_1") (pintype "input"))
    )
    (net (code "88") (name "Net-(U5A-O)") (class "Default")
      (node (ref "R43") (pin "1") (pinfunction "1_1") (pintype "passive"))
      (node (ref "U5") (pin "2") (pinfunction "O_2") (pintype "output"))
    )
    (net (code "89") (name "Net-(U5B-I)") (class "Default")
      (node (ref "D20") (pin "A") (pinfunction "A_A") (pintype "passive"))
      (node (ref "R38") (pin "2") (pinfunction "2_2") (pintype "passive"))
      (node (ref "U5") (pin "3") (pinfunction "I_3") (pintype "input"))
    )
    (net (code "90") (name "Net-(U5B-O)") (class "Default")
      (node (ref "R44") (pin "1") (pinfunction "1_1") (pintype "passive"))
      (node (ref "U5") (pin "4") (pinfunction "O_4") (pintype "output"))
    )
    (net (code "91") (name "Net-(U5C-I)") (class "Default")
      (node (ref "D21") (pin "A") (pinfunction "A_A") (pintype "passive"))
      (node (ref "R39") (pin "2") (pinfunction "2_2") (pintype "passive"))
      (node (ref "U5") (pin "5") (pinfunction "I_5") (pintype "input"))
    )
    (net (code "92") (name "Net-(U5C-O)") (class "Default")
      (node (ref "R45") (pin "1") (pinfunction "1_1") (pintype "passive"))
      (node (ref "U5") (pin "6") (pinfunction "O_6") (pintype "output"))
    )
    (net (code "93") (name "Net-(U5D-I)") (class "Default")
      (node (ref "D22") (pin "A") (pinfunction "A_A") (pintype "passive"))
      (node (ref "R40") (pin "2") (pinfunction "2_2") (pintype "passive"))
      (node (ref "U5") (pin "9") (pinfunction "I_9") (pintype "input"))
    )
    (net (code "94") (name "Net-(U5D-O)") (class "Default")
      (node (ref "R46") (pin "1") (pinfunction "1_1") (pintype "passive"))
      (node (ref "U5") (pin "8") (pinfunction "O_8") (pintype "output"))
    )
    (net (code "95") (name "Net-(U5E-I)") (class "Default")
      (node (ref "D23") (pin "A") (pinfunction "A_A") (pintype "passive"))
      (node (ref "R41") (pin "2") (pinfunction "2_2") (pintype "passive"))
      (node (ref "U5") (pin "11") (pinfunction "I_11") (pintype "input"))
    )
    (net (code "96") (name "Net-(U5E-O)") (class "Default")
      (node (ref "R47") (pin "1") (pinfunction "1_1") (pintype "passive"))
      (node (ref "U5") (pin "10") (pinfunction "O_10") (pintype "output"))
    )
    (net (code "97") (name "Net-(U5F-I)") (class "Default")
      (node (ref "D24") (pin "A") (pinfunction "A_A") (pintype "passive"))
      (node (ref "R42") (pin "2") (pinfunction "2_2") (pintype "passive"))
      (node (ref "U5") (pin "13") (pinfunction "I_13") (pintype "input"))
    )
    (net (code "98") (name "Net-(U5F-O)") (class "Default")
      (node (ref "R48") (pin "1") (pinfunction "1_1") (pintype "passive"))
      (node (ref "U5") (pin "12") (pinfunction "O_12") (pintype "output"))
    )
  )
)
